# SW6124_A_A_C_MCU_LED.net
KiCad netlist of a schematic drawn in Altium Designer
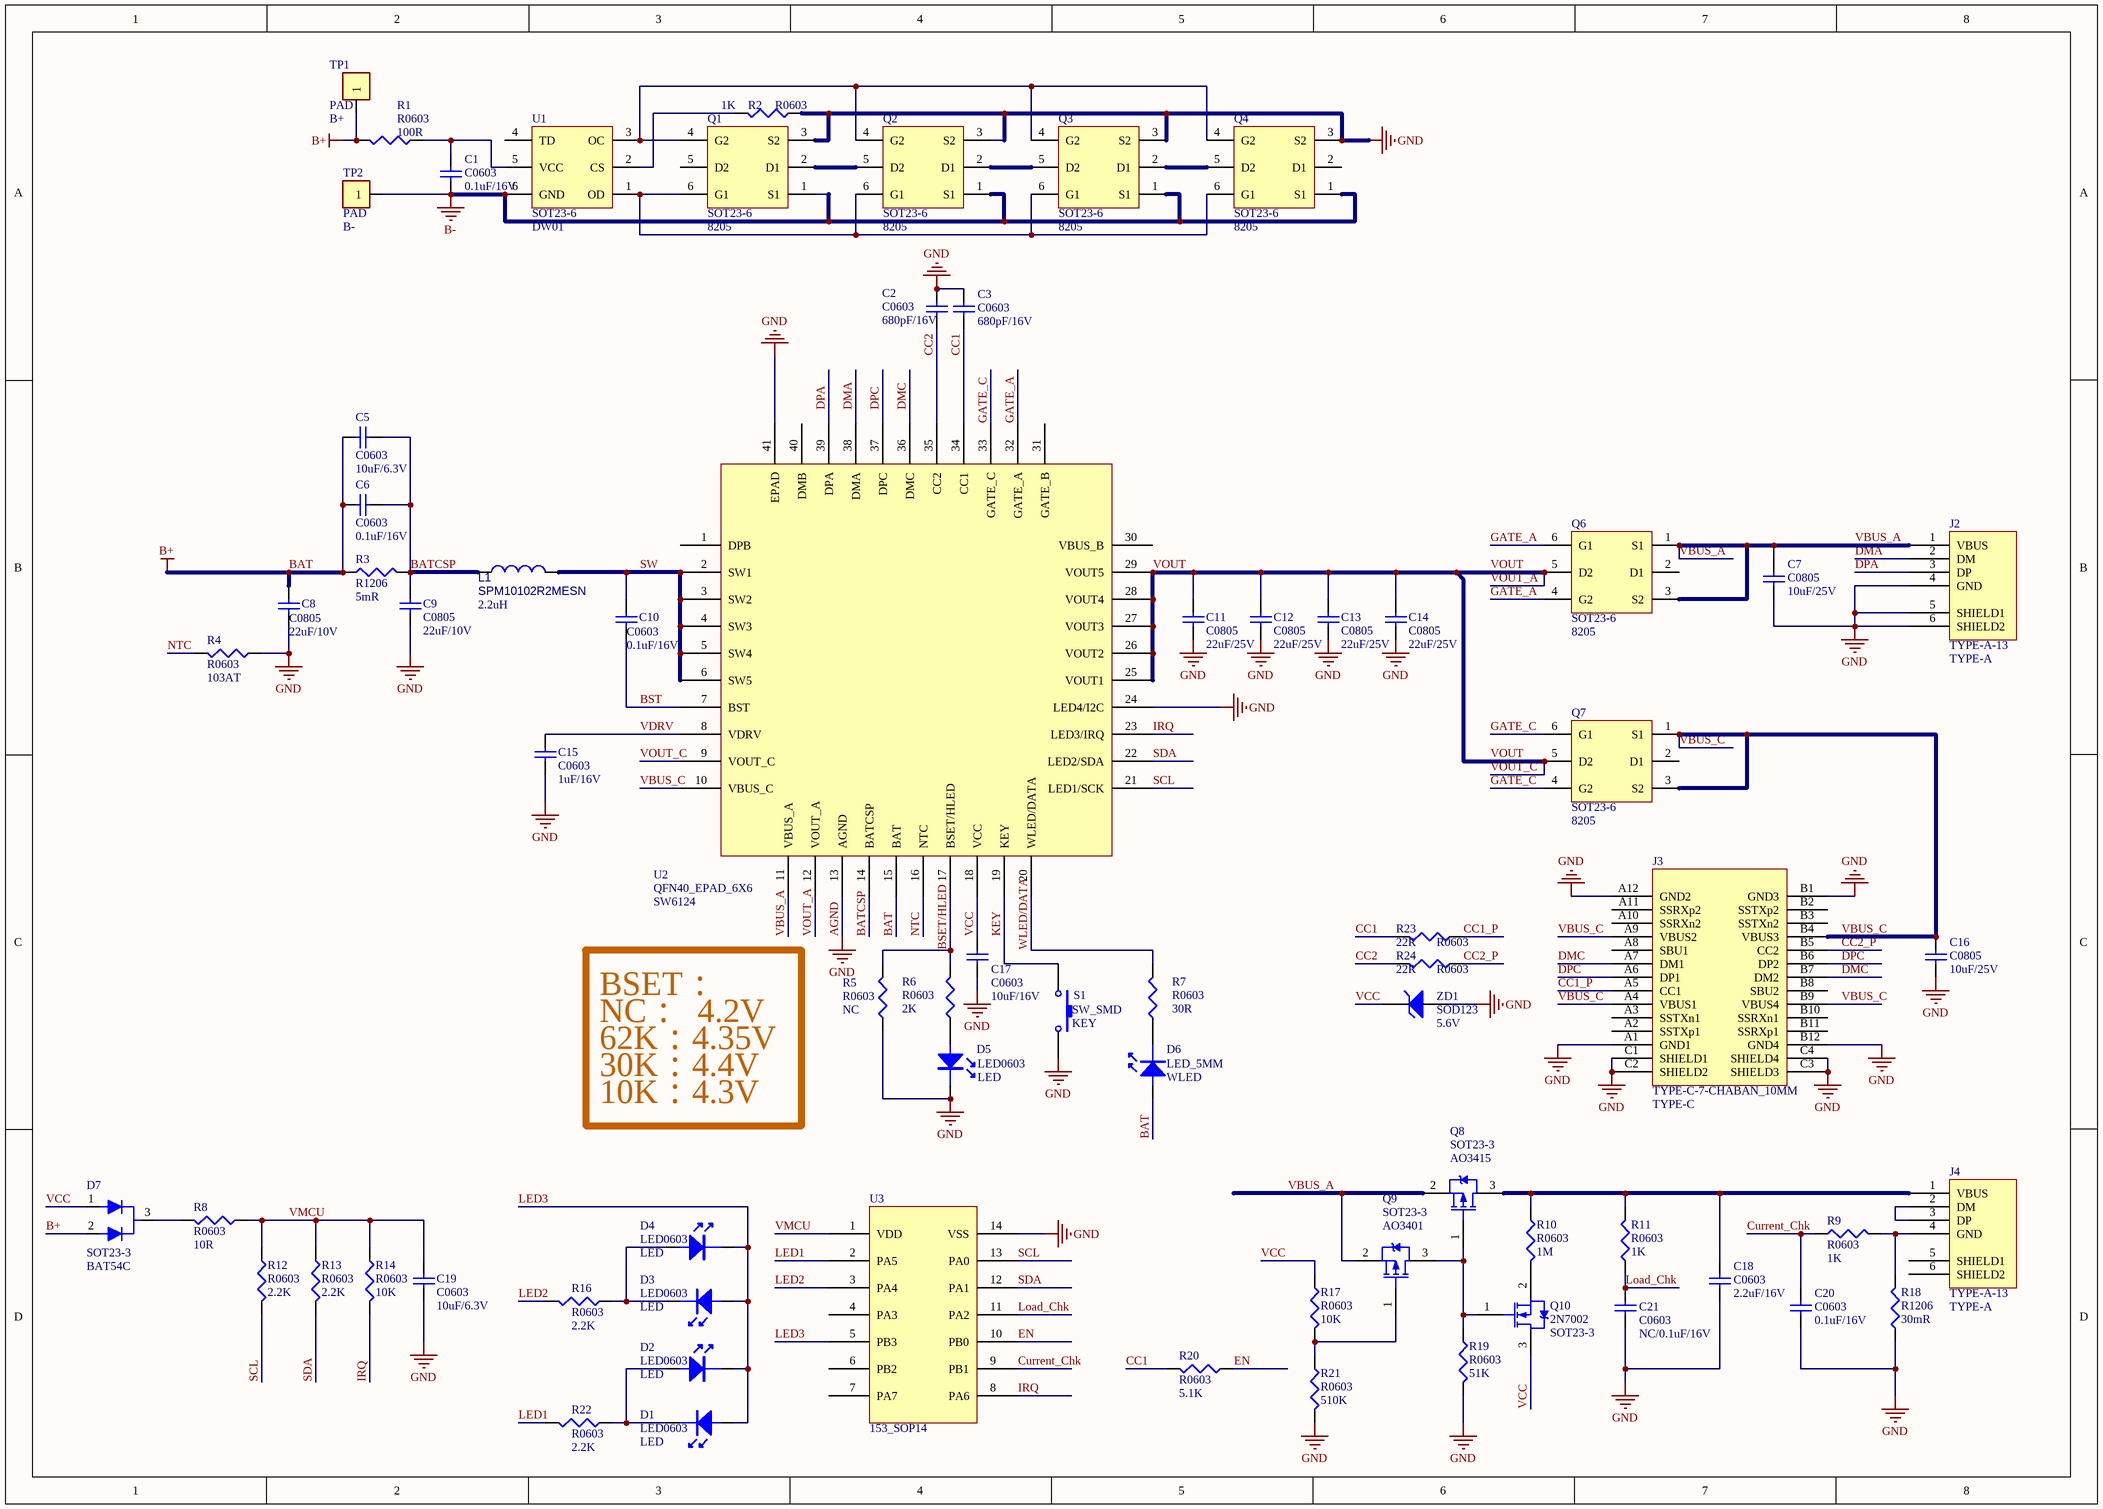
[diagram p0: SW6124+A+A+C+MCU+LED.SchDoc]

(export (version "E")
  (design (tool "Eeschema 10.0.6"))
  (components
    (comp (ref "C1")
      (value "C0603")
      (footprint "C0603")
      (description "Capacitor")
      (fields (field (name "ALTIUM_VALUE") "0.1uF/16V") (field (name "PUBLISHER") "Altium Limited"))
      (libsource (lib "*") (part "Cap"))
    )
    (comp (ref "C2")
      (value "C0603")
      (footprint "C0603")
      (description "Capacitor")
      (fields (field (name "ALTIUM_VALUE") "680pF/16V") (field (name "PUBLISHER") "Altium Limited"))
      (libsource (lib "*") (part "CAP0603"))
    )
    (comp (ref "C3")
      (value "C0603")
      (footprint "C0603")
      (description "Capacitor")
      (fields (field (name "ALTIUM_VALUE") "680pF/16V") (field (name "PUBLISHER") "Altium Limited"))
      (libsource (lib "*") (part "CAP0603"))
    )
    (comp (ref "C5")
      (value "C0603")
      (footprint "C0603")
      (description "Capacitor")
      (fields (field (name "ALTIUM_VALUE") "10uF/6.3V") (field (name "PUBLISHER") "Altium Limited"))
      (libsource (lib "*") (part "CAP0603"))
    )
    (comp (ref "C6")
      (value "C0603")
      (footprint "C0603")
      (description "Capacitor")
      (fields (field (name "ALTIUM_VALUE") "0.1uF/16V") (field (name "PUBLISHER") "Altium Limited"))
      (libsource (lib "*") (part "CAP0603"))
    )
    (comp (ref "C7")
      (value "C0805")
      (footprint "C0805")
      (description "Capacitor")
      (fields (field (name "ALTIUM_VALUE") "10uF/25V") (field (name "PUBLISHER") "Altium Limited"))
      (libsource (lib "*") (part "CAP0603"))
    )
    (comp (ref "C8")
      (value "C0805")
      (footprint "C0805")
      (description "Capacitor")
      (fields (field (name "ALTIUM_VALUE") "22uF/10V") (field (name "PUBLISHER") "Altium Limited"))
      (libsource (lib "*") (part "CAP0805"))
    )
    (comp (ref "C9")
      (value "C0805")
      (footprint "C0805")
      (description "Capacitor")
      (fields (field (name "ALTIUM_VALUE") "22uF/10V") (field (name "PUBLISHER") "Altium Limited"))
      (libsource (lib "*") (part "CAP0805"))
    )
    (comp (ref "C10")
      (value "C0603")
      (footprint "C0603")
      (description "Capacitor")
      (fields (field (name "ALTIUM_VALUE") "0.1uF/16V") (field (name "PUBLISHER") "Altium Limited"))
      (libsource (lib "*") (part "CAP0603"))
    )
    (comp (ref "C11")
      (value "C0805")
      (footprint "C0805")
      (description "Capacitor")
      (fields (field (name "ALTIUM_VALUE") "22uF/25V") (field (name "PUBLISHER") "Altium Limited"))
      (libsource (lib "*") (part "CAP0805"))
    )
    (comp (ref "C12")
      (value "C0805")
      (footprint "C0805")
      (description "Capacitor")
      (fields (field (name "ALTIUM_VALUE") "22uF/25V") (field (name "PUBLISHER") "Altium Limited"))
      (libsource (lib "*") (part "CAP0805"))
    )
    (comp (ref "C13")
      (value "C0805")
      (footprint "C0805")
      (description "Capacitor")
      (fields (field (name "ALTIUM_VALUE") "22uF/25V") (field (name "PUBLISHER") "Altium Limited"))
      (libsource (lib "*") (part "CAP0805"))
    )
    (comp (ref "C14")
      (value "C0805")
      (footprint "C0805")
      (description "Capacitor")
      (fields (field (name "ALTIUM_VALUE") "22uF/25V") (field (name "PUBLISHER") "Altium Limited"))
      (libsource (lib "*") (part "CAP0805"))
    )
    (comp (ref "C15")
      (value "C0603")
      (footprint "C0603")
      (description "Capacitor")
      (fields (field (name "ALTIUM_VALUE") "1uF/16V") (field (name "PUBLISHER") "Altium Limited"))
      (libsource (lib "*") (part "CAP0603"))
    )
    (comp (ref "C16")
      (value "C0805")
      (footprint "C0805")
      (description "Capacitor")
      (fields (field (name "ALTIUM_VALUE") "10uF/25V") (field (name "PUBLISHER") "Altium Limited"))
      (libsource (lib "*") (part "CAP0603"))
    )
    (comp (ref "C17")
      (value "C0603")
      (footprint "C0603")
      (description "Capacitor")
      (fields (field (name "ALTIUM_VALUE") "10uF/16V") (field (name "PUBLISHER") "Altium Limited"))
      (libsource (lib "*") (part "CAP0603"))
    )
    (comp (ref "C18")
      (value "C0603")
      (footprint "C0603")
      (description "Capacitor")
      (fields (field (name "ALTIUM_VALUE") "2.2uF/16V") (field (name "PUBLISHER") "Altium Limited"))
      (libsource (lib "*") (part "CAP0603"))
    )
    (comp (ref "C19")
      (value "C0603")
      (footprint "C0603")
      (description "Capacitor")
      (fields (field (name "ALTIUM_VALUE") "10uF/6.3V") (field (name "PUBLISHER") "Altium Limited"))
      (libsource (lib "*") (part "CAP0603"))
    )
    (comp (ref "C20")
      (value "C0603")
      (footprint "C0603")
      (description "Capacitor")
      (fields (field (name "ALTIUM_VALUE") "0.1uF/16V") (field (name "PUBLISHER") "Altium Limited"))
      (libsource (lib "*") (part "CAP0603"))
    )
    (comp (ref "C21")
      (value "C0603")
      (footprint "C0603")
      (description "Capacitor")
      (fields (field (name "ALTIUM_VALUE") "NC/0.1uF/16V") (field (name "PUBLISHER") "Altium Limited"))
      (libsource (lib "*") (part "CAP0603"))
    )
    (comp (ref "D1") (value "LED") (footprint "LED0603") (libsource (lib "*") (part "LED")))
    (comp (ref "D2") (value "LED") (footprint "LED0603") (libsource (lib "*") (part "LED")))
    (comp (ref "D3") (value "LED") (footprint "LED0603") (libsource (lib "*") (part "LED")))
    (comp (ref "D4") (value "LED") (footprint "LED0603") (libsource (lib "*") (part "LED")))
    (comp (ref "D5") (value "LED") (footprint "LED0603") (libsource (lib "*") (part "LED")))
    (comp (ref "D6")
      (value "WLED")
      (footprint "LED_5MM")
      (fields (field (name "FOOTPRINF") "LED_5MM") (field (name "Comment") "LED_5MM"))
      (libsource (lib "*") (part "LED"))
    )
    (comp (ref "D7") (value "BAT54C") (footprint "SOT23-3") (libsource (lib "Schlib1-2012") (part "D3")))
    (comp (ref "J2")
      (value "TYPE-A")
      (footprint "TYPE-A-13")
      (fields (field (name "FOOTPRINF") "TYPE-A-13") (field (name "Comment") "TYPE-A-1"))
      (libsource (lib "*") (part "TYPE-A-1"))
    )
    (comp (ref "J3")
      (value "TYPE-C")
      (footprint "TYPE-C-7-CHABAN_10MM")
      (libsource (lib "*") (part "TYPE-C"))
    )
    (comp (ref "J4")
      (value "TYPE-A")
      (footprint "PIE10-USB")
      (fields (field (name "FOOTPRINF") "TYPE-A-13") (field (name "Comment") "TYPE-A-1"))
      (libsource (lib "*") (part "TYPE-A-1"))
    )
    (comp (ref "L1")
      (value "SPM10102R2MESN")
      (footprint "INDUCTOR_SPM1010")
      (fields (field (name "ALTIUM_VALUE") "2.2uH"))
      (libsource (lib "*") (part "INDUCTOR"))
    )
    (comp (ref "Q1")
      (value "8205")
      (footprint "SOT23-6")
      (fields (field (name "FOOTPRINF") "SOT23-6"))
      (libsource (lib "") (part "8205B_1"))
    )
    (comp (ref "Q2")
      (value "8205")
      (footprint "SOT23-6")
      (fields (field (name "FOOTPRINF") "SOT23-6"))
      (libsource (lib "") (part "8205B_1"))
    )
    (comp (ref "Q3")
      (value "8205")
      (footprint "SOT23-6")
      (fields (field (name "FOOTPRINF") "SOT23-6"))
      (libsource (lib "") (part "8205B_1"))
    )
    (comp (ref "Q4")
      (value "8205")
      (footprint "SOT23-6")
      (fields (field (name "FOOTPRINF") "SOT23-6"))
      (libsource (lib "") (part "8205B_1"))
    )
    (comp (ref "Q6")
      (value "8205")
      (footprint "SOT23-6")
      (fields (field (name "FOOTPRINF") "SOT23-6"))
      (libsource (lib "*") (part "8205B"))
    )
    (comp (ref "Q7")
      (value "8205")
      (footprint "SOT23-6")
      (fields (field (name "FOOTPRINF") "SOT23-6"))
      (libsource (lib "*") (part "8205B"))
    )
    (comp (ref "Q8")
      (value "AO3415")
      (footprint "SOT23-3")
      (description "P-Channel Power MOSFET")
      (fields (field (name "Comment") "PMOS-2") (field (name "PUBLISHER") "Altium Limited"))
      (libsource (lib "Miscellaneous Devices") (part "PMOS-2"))
    )
    (comp (ref "Q9")
      (value "AO3401")
      (footprint "SOT23-3")
      (description "P-Channel Power MOSFET")
      (fields (field (name "Comment") "PMOS-2") (field (name "PUBLISHER") "Altium Limited"))
      (libsource (lib "Miscellaneous Devices") (part "PMOS-2"))
    )
    (comp (ref "Q10")
      (value "2N7002")
      (footprint "SOT23-3")
      (description "N-Channel Power MOSFET")
      (fields (field (name "Comment") "NMOS-2") (field (name "PUBLISHER") "Altium Limited"))
      (libsource (lib "Miscellaneous Devices") (part "NMOS-2"))
    )
    (comp (ref "R1")
      (value "R0603")
      (footprint "R0603")
      (description "Resistor")
      (fields (field (name "ALTIUM_VALUE") "100R") (field (name "PUBLISHER") "Altium Limited"))
      (libsource (lib "*") (part "Res3"))
    )
    (comp (ref "R2")
      (value "R0603")
      (footprint "R0603")
      (description "Resistor")
      (fields (field (name "ALTIUM_VALUE") "1K") (field (name "PUBLISHER") "Altium Limited"))
      (libsource (lib "*") (part "Res3"))
    )
    (comp (ref "R3")
      (value "R1206")
      (footprint "R1206")
      (description "Resistor")
      (fields (field (name "ALTIUM_VALUE") "5mR") (field (name "PUBLISHER") "Altium Limited"))
      (libsource (lib "*") (part "RES"))
    )
    (comp (ref "R4")
      (value "R0603")
      (footprint "R0603")
      (description "Resistor")
      (fields (field (name "ALTIUM_VALUE") "103AT") (field (name "PUBLISHER") "Altium Limited"))
      (libsource (lib "*") (part "RES"))
    )
    (comp (ref "R5")
      (value "R0603")
      (footprint "R0603")
      (description "Resistor")
      (fields (field (name "ALTIUM_VALUE") "NC") (field (name "PUBLISHER") "Altium Limited"))
      (libsource (lib "*") (part "RES"))
    )
    (comp (ref "R6")
      (value "R0603")
      (footprint "R0603")
      (description "Resistor")
      (fields (field (name "ALTIUM_VALUE") "2K") (field (name "PUBLISHER") "Altium Limited"))
      (libsource (lib "*") (part "RES"))
    )
    (comp (ref "R7")
      (value "R0603")
      (footprint "R0603")
      (description "Resistor")
      (fields (field (name "ALTIUM_VALUE") "30R") (field (name "PUBLISHER") "Altium Limited"))
      (libsource (lib "*") (part "RES"))
    )
    (comp (ref "R8")
      (value "R0603")
      (footprint "R0603")
      (description "Resistor")
      (fields (field (name "ALTIUM_VALUE") "10R") (field (name "PUBLISHER") "Altium Limited"))
      (libsource (lib "*") (part "RES"))
    )
    (comp (ref "R9")
      (value "R0603")
      (footprint "R0603")
      (description "Resistor")
      (fields (field (name "ALTIUM_VALUE") "1K") (field (name "PUBLISHER") "Altium Limited"))
      (libsource (lib "*") (part "RES"))
    )
    (comp (ref "R10")
      (value "R0603")
      (footprint "R0603")
      (description "Resistor")
      (fields (field (name "ALTIUM_VALUE") "1M") (field (name "PUBLISHER") "Altium Limited"))
      (libsource (lib "*") (part "RES"))
    )
    (comp (ref "R11")
      (value "R0603")
      (footprint "R0603")
      (description "Resistor")
      (fields (field (name "ALTIUM_VALUE") "1K") (field (name "PUBLISHER") "Altium Limited"))
      (libsource (lib "*") (part "RES"))
    )
    (comp (ref "R12")
      (value "R0603")
      (footprint "R0603")
      (description "Resistor")
      (fields (field (name "ALTIUM_VALUE") "2.2K") (field (name "PUBLISHER") "Altium Limited"))
      (libsource (lib "*") (part "RES"))
    )
    (comp (ref "R13")
      (value "R0603")
      (footprint "R0603")
      (description "Resistor")
      (fields (field (name "ALTIUM_VALUE") "2.2K") (field (name "PUBLISHER") "Altium Limited"))
      (libsource (lib "*") (part "RES"))
    )
    (comp (ref "R14")
      (value "R0603")
      (footprint "R0603")
      (description "Resistor")
      (fields (field (name "ALTIUM_VALUE") "10K") (field (name "PUBLISHER") "Altium Limited"))
      (libsource (lib "*") (part "RES"))
    )
    (comp (ref "R16")
      (value "R0603")
      (footprint "R0603")
      (description "Resistor")
      (fields (field (name "ALTIUM_VALUE") "2.2K") (field (name "PUBLISHER") "Altium Limited"))
      (libsource (lib "*") (part "RES"))
    )
    (comp (ref "R17")
      (value "R0603")
      (footprint "R0603")
      (description "Resistor")
      (fields (field (name "ALTIUM_VALUE") "10K") (field (name "PUBLISHER") "Altium Limited"))
      (libsource (lib "*") (part "RES"))
    )
    (comp (ref "R18")
      (value "R1206")
      (footprint "C-1206A")
      (description "Resistor")
      (fields (field (name "ALTIUM_VALUE") "30mR") (field (name "PUBLISHER") "Altium Limited"))
      (libsource (lib "*") (part "RES"))
    )
    (comp (ref "R19")
      (value "R0603")
      (footprint "R0603")
      (description "Resistor")
      (fields (field (name "ALTIUM_VALUE") "51K") (field (name "PUBLISHER") "Altium Limited"))
      (libsource (lib "*") (part "RES"))
    )
    (comp (ref "R20")
      (value "R0603")
      (footprint "R0603")
      (description "Resistor")
      (fields (field (name "ALTIUM_VALUE") "5.1K") (field (name "PUBLISHER") "Altium Limited"))
      (libsource (lib "*") (part "RES"))
    )
    (comp (ref "R21")
      (value "R0603")
      (footprint "R0603")
      (description "Resistor")
      (fields (field (name "ALTIUM_VALUE") "510K") (field (name "PUBLISHER") "Altium Limited"))
      (libsource (lib "*") (part "RES"))
    )
    (comp (ref "R22")
      (value "R0603")
      (footprint "R0603")
      (description "Resistor")
      (fields (field (name "ALTIUM_VALUE") "2.2K") (field (name "PUBLISHER") "Altium Limited"))
      (libsource (lib "*") (part "RES"))
    )
    (comp (ref "R23")
      (value "R0603")
      (footprint "R0603")
      (description "Resistor")
      (fields (field (name "ALTIUM_VALUE") "22R") (field (name "PUBLISHER") "Altium Limited"))
      (libsource (lib "*") (part "RES"))
    )
    (comp (ref "R24")
      (value "R0603")
      (footprint "R0603")
      (description "Resistor")
      (fields (field (name "ALTIUM_VALUE") "22R") (field (name "PUBLISHER") "Altium Limited"))
      (libsource (lib "*") (part "RES"))
    )
    (comp (ref "S1")
      (value "KEY")
      (footprint "SW_SMD")
      (fields (field (name "FOOTPRINF") "SW_SMD"))
      (libsource (lib "*") (part "SW K"))
    )
    (comp (ref "TP1") (value "B+") (footprint "PAD") (libsource (lib "") (part "Test Point_1")))
    (comp (ref "TP2") (value "B-") (footprint "PAD") (libsource (lib "*") (part "Test Point")))
    (comp (ref "U1")
      (value "DW01")
      (footprint "SOT23-6")
      (fields (field (name "FOOTPRINF") "SOT23-6"))
      (libsource (lib "*") (part "DW01"))
    )
    (comp (ref "U2")
      (value "SW6124")
      (footprint "QFN40_EPAD_6X6")
      (libsource (lib "TEST") (part "SW6106_AFC"))
    )
    (comp (ref "U3") (value "153_SOP14") (libsource (lib "TEST") (part "153_SOP14")))
    (comp (ref "ZD1")
      (value "SOD123")
      (footprint "SOD-123")
      (description "Zener Diode")
      (fields (field (name "ALTIUM_UNNAMED_1") "5.6V"))
      (libsource (lib "Miscellaneous Devices") (part "D Zener"))
    )
  )
  (nets
    (net (code "1") (name "/BATCSP") (class "Default")
      (node (ref "C5") (pin "2") (pinfunction "2_2") (pintype "passive"))
      (node (ref "C6") (pin "2") (pinfunction "2_2") (pintype "passive"))
      (node (ref "C9") (pin "2") (pinfunction "2_2") (pintype "passive"))
      (node (ref "L1") (pin "1") (pinfunction "1_1") (pintype "passive"))
      (node (ref "R3") (pin "2") (pinfunction "2_2") (pintype "passive"))
      (node (ref "U2") (pin "14") (pinfunction "BATCSP_14") (pintype "passive"))
    )
    (net (code "2") (name "/BSET{slash}HLED") (class "Default")
      (node (ref "R5") (pin "2") (pinfunction "2_2") (pintype "passive"))
      (node (ref "R6") (pin "2") (pinfunction "2_2") (pintype "passive"))
      (node (ref "U2") (pin "17") (pinfunction "BSET/HLED_17") (pintype "passive"))
    )
    (net (code "3") (name "/BST") (class "Default")
      (node (ref "C10") (pin "1") (pinfunction "1_1") (pintype "passive"))
      (node (ref "U2") (pin "7") (pinfunction "BST_7") (pintype "passive"))
    )
    (net (code "4") (name "/CC1") (class "Default")
      (node (ref "C3") (pin "1") (pinfunction "1_1") (pintype "passive"))
      (node (ref "R20") (pin "2") (pinfunction "2_2") (pintype "passive"))
      (node (ref "R23") (pin "2") (pinfunction "2_2") (pintype "passive"))
      (node (ref "U2") (pin "34") (pinfunction "CC1_34") (pintype "passive"))
    )
    (net (code "5") (name "/CC1_P") (class "Default")
      (node (ref "J3") (pin "A5") (pinfunction "CC1_A5") (pintype "passive"))
      (node (ref "R23") (pin "1") (pinfunction "1_1") (pintype "passive"))
    )
    (net (code "6") (name "/CC2") (class "Default")
      (node (ref "C2") (pin "1") (pinfunction "1_1") (pintype "passive"))
      (node (ref "R24") (pin "2") (pinfunction "2_2") (pintype "passive"))
      (node (ref "U2") (pin "35") (pinfunction "CC2_35") (pintype "passive"))
    )
    (net (code "7") (name "/CC2_P") (class "Default")
      (node (ref "J3") (pin "B5") (pinfunction "CC2_B5") (pintype "passive"))
      (node (ref "R24") (pin "1") (pinfunction "1_1") (pintype "passive"))
    )
    (net (code "8") (name "/Current_Chk") (class "Default")
      (node (ref "C20") (pin "2") (pinfunction "2_2") (pintype "passive"))
      (node (ref "R9") (pin "1") (pinfunction "1_1") (pintype "passive"))
      (node (ref "U3") (pin "9") (pinfunction "PB1_9") (pintype "passive"))
    )
    (net (code "9") (name "/DMA") (class "Default")
      (node (ref "J2") (pin "2") (pinfunction "DM_2") (pintype "passive"))
      (node (ref "U2") (pin "38") (pinfunction "DMA_38") (pintype "passive"))
    )
    (net (code "10") (name "/DMC") (class "Default")
      (node (ref "J3") (pin "A7") (pinfunction "DM1_A7") (pintype "passive"))
      (node (ref "J3") (pin "B7") (pinfunction "DM2_B7") (pintype "passive"))
      (node (ref "U2") (pin "36") (pinfunction "DMC_36") (pintype "passive"))
    )
    (net (code "11") (name "/DPA") (class "Default")
      (node (ref "J2") (pin "3") (pinfunction "DP_3") (pintype "passive"))
      (node (ref "U2") (pin "39") (pinfunction "DPA_39") (pintype "passive"))
    )
    (net (code "12") (name "/DPC") (class "Default")
      (node (ref "J3") (pin "A6") (pinfunction "DP1_A6") (pintype "passive"))
      (node (ref "J3") (pin "B6") (pinfunction "DP2_B6") (pintype "passive"))
      (node (ref "U2") (pin "37") (pinfunction "DPC_37") (pintype "passive"))
    )
    (net (code "13") (name "/EN") (class "Default")
      (node (ref "R20") (pin "1") (pinfunction "1_1") (pintype "passive"))
      (node (ref "U3") (pin "10") (pinfunction "PB0_10") (pintype "passive"))
    )
    (net (code "14") (name "/GATE_A") (class "Default")
      (node (ref "Q6") (pin "4") (pinfunction "G2_4") (pintype "passive"))
      (node (ref "Q6") (pin "6") (pinfunction "G1_6") (pintype "passive"))
      (node (ref "U2") (pin "32") (pinfunction "GATE_A_32") (pintype "passive"))
    )
    (net (code "15") (name "/GATE_C") (class "Default")
      (node (ref "Q7") (pin "4") (pinfunction "G2_4") (pintype "passive"))
      (node (ref "Q7") (pin "6") (pinfunction "G1_6") (pintype "passive"))
      (node (ref "U2") (pin "33") (pinfunction "GATE_C_33") (pintype "passive"))
    )
    (net (code "16") (name "/IRQ") (class "Default")
      (node (ref "R14") (pin "2") (pinfunction "2_2") (pintype "passive"))
      (node (ref "U2") (pin "23") (pinfunction "LED3/IRQ_23") (pintype "passive"))
      (node (ref "U3") (pin "8") (pinfunction "PA6_8") (pintype "passive"))
    )
    (net (code "17") (name "/KEY") (class "Default")
      (node (ref "S1") (pin "1") (pinfunction "1_1") (pintype "passive"))
      (node (ref "U2") (pin "19") (pinfunction "KEY_19") (pintype "passive"))
    )
    (net (code "18") (name "/LED1") (class "Default")
      (node (ref "R22") (pin "2") (pinfunction "2_2") (pintype "passive"))
      (node (ref "U3") (pin "2") (pinfunction "PA5_2") (pintype "passive"))
    )
    (net (code "19") (name "/LED2") (class "Default")
      (node (ref "R16") (pin "2") (pinfunction "2_2") (pintype "passive"))
      (node (ref "U3") (pin "3") (pinfunction "PA4_3") (pintype "passive"))
    )
    (net (code "20") (name "/LED3") (class "Default")
      (node (ref "D1") (pin "1") (pinfunction "A_1") (pintype "passive"))
      (node (ref "D2") (pin "2") (pinfunction "K_2") (pintype "passive"))
      (node (ref "D3") (pin "1") (pinfunction "A_1") (pintype "passive"))
      (node (ref "D4") (pin "2") (pinfunction "K_2") (pintype "passive"))
      (node (ref "U3") (pin "5") (pinfunction "PB3_5") (pintype "passive"))
    )
    (net (code "21") (name "/Load_Chk") (class "Default")
      (node (ref "C21") (pin "2") (pinfunction "2_2") (pintype "passive"))
      (node (ref "R11") (pin "1") (pinfunction "1_1") (pintype "passive"))
      (node (ref "U3") (pin "11") (pinfunction "PA2_11") (pintype "passive"))
    )
    (net (code "22") (name "/NTC") (class "Default")
      (node (ref "R4") (pin "2") (pinfunction "2_2") (pintype "passive"))
      (node (ref "U2") (pin "16") (pinfunction "NTC_16") (pintype "passive"))
    )
    (net (code "23") (name "/SCL") (class "Default")
      (node (ref "R12") (pin "2") (pinfunction "2_2") (pintype "passive"))
      (node (ref "U2") (pin "21") (pinfunction "LED1/SCK_21") (pintype "passive"))
      (node (ref "U3") (pin "13") (pinfunction "PA0_13") (pintype "passive"))
    )
    (net (code "24") (name "/SDA") (class "Default")
      (node (ref "R13") (pin "2") (pinfunction "2_2") (pintype "passive"))
      (node (ref "U2") (pin "22") (pinfunction "LED2/SDA_22") (pintype "passive"))
      (node (ref "U3") (pin "12") (pinfunction "PA1_12") (pintype "passive"))
    )
    (net (code "25") (name "/SW") (class "Default")
      (node (ref "C10") (pin "2") (pinfunction "2_2") (pintype "passive"))
      (node (ref "L1") (pin "2") (pinfunction "2_2") (pintype "passive"))
      (node (ref "U2") (pin "2") (pinfunction "SW1_2") (pintype "passive"))
      (node (ref "U2") (pin "3") (pinfunction "SW2_3") (pintype "passive"))
      (node (ref "U2") (pin "4") (pinfunction "SW3_4") (pintype "passive"))
      (node (ref "U2") (pin "5") (pinfunction "SW4_5") (pintype "passive"))
      (node (ref "U2") (pin "6") (pinfunction "SW5_6") (pintype "passive"))
    )
    (net (code "26") (name "/VBUS_A") (class "Default")
      (node (ref "C7") (pin "2") (pinfunction "2_2") (pintype "passive"))
      (node (ref "J2") (pin "1") (pinfunction "VBUS_1") (pintype "passive"))
      (node (ref "Q6") (pin "1") (pinfunction "S1_1") (pintype "passive"))
      (node (ref "Q6") (pin "3") (pinfunction "S2_3") (pintype "passive"))
      (node (ref "Q8") (pin "2") (pinfunction "S_2") (pintype "passive"))
      (node (ref "Q9") (pin "2") (pinfunction "S_2") (pintype "passive"))
      (node (ref "U2") (pin "11") (pinfunction "VBUS_A_11") (pintype "passive"))
    )
    (net (code "27") (name "/VBUS_C") (class "Default")
      (node (ref "C16") (pin "2") (pinfunction "2_2") (pintype "passive"))
      (node (ref "J3") (pin "A4") (pinfunction "VBUS1_A4") (pintype "passive"))
      (node (ref "J3") (pin "A9") (pinfunction "VBUS2_A9") (pintype "passive"))
      (node (ref "J3") (pin "B4") (pinfunction "VBUS3_B4") (pintype "passive"))
      (node (ref "J3") (pin "B9") (pinfunction "VBUS4_B9") (pintype "passive"))
      (node (ref "Q7") (pin "1") (pinfunction "S1_1") (pintype "passive"))
      (node (ref "Q7") (pin "3") (pinfunction "S2_3") (pintype "passive"))
      (node (ref "U2") (pin "10") (pinfunction "VBUS_C_10") (pintype "passive"))
    )
    (net (code "28") (name "/VCC") (class "Default")
      (node (ref "C17") (pin "2") (pinfunction "2_2") (pintype "passive"))
      (node (ref "D7") (pin "1") (pintype "passive"))
      (node (ref "Q10") (pin "3") (pinfunction "D_3") (pintype "passive"))
      (node (ref "R17") (pin "1") (pinfunction "1_1") (pintype "passive"))
      (node (ref "U2") (pin "18") (pinfunction "VCC_18") (pintype "passive"))
      (node (ref "ZD1") (pin "2") (pinfunction "K_2") (pintype "passive"))
    )
    (net (code "29") (name "/VDRV") (class "Default")
      (node (ref "C15") (pin "2") (pinfunction "2_2") (pintype "passive"))
      (node (ref "U2") (pin "8") (pinfunction "VDRV_8") (pintype "passive"))
    )
    (net (code "30") (name "/VMCU") (class "Default")
      (node (ref "C19") (pin "1") (pinfunction "1_1") (pintype "passive"))
      (node (ref "R12") (pin "1") (pinfunction "1_1") (pintype "passive"))
      (node (ref "R13") (pin "1") (pinfunction "1_1") (pintype "passive"))
      (node (ref "R14") (pin "1") (pinfunction "1_1") (pintype "passive"))
      (node (ref "R8") (pin "1") (pinfunction "1_1") (pintype "passive"))
      (node (ref "U3") (pin "1") (pinfunction "VDD_1") (pintype "passive"))
    )
    (net (code "31") (name "/VOUT") (class "Default")
      (node (ref "C11") (pin "2") (pinfunction "2_2") (pintype "passive"))
      (node (ref "C12") (pin "2") (pinfunction "2_2") (pintype "passive"))
      (node (ref "C13") (pin "2") (pinfunction "2_2") (pintype "passive"))
      (node (ref "C14") (pin "2") (pinfunction "2_2") (pintype "passive"))
      (node (ref "Q6") (pin "5") (pinfunction "D2_5") (pintype "passive"))
      (node (ref "Q7") (pin "5") (pinfunction "D2_5") (pintype "passive"))
      (node (ref "U2") (pin "12") (pinfunction "VOUT_A_12") (pintype "passive"))
      (node (ref "U2") (pin "25") (pinfunction "VOUT1_25") (pintype "passive"))
      (node (ref "U2") (pin "26") (pinfunction "VOUT2_26") (pintype "passive"))
      (node (ref "U2") (pin "27") (pinfunction "VOUT3_27") (pintype "passive"))
      (node (ref "U2") (pin "28") (pinfunction "VOUT4_28") (pintype "passive"))
      (node (ref "U2") (pin "29") (pinfunction "VOUT5_29") (pintype "passive"))
      (node (ref "U2") (pin "9") (pinfunction "VOUT_C_9") (pintype "passive"))
    )
    (net (code "32") (name "/WLED{slash}DATA") (class "Default")
      (node (ref "R7") (pin "2") (pinfunction "2_2") (pintype "passive"))
      (node (ref "U2") (pin "20") (pinfunction "WLED/DATA_20") (pintype "passive"))
    )
    (net (code "33") (name "B+") (class "Default")
      (node (ref "C5") (pin "1") (pinfunction "1_1") (pintype "passive"))
      (node (ref "C6") (pin "1") (pinfunction "1_1") (pintype "passive"))
      (node (ref "C8") (pin "2") (pinfunction "2_2") (pintype "passive"))
      (node (ref "D6") (pin "1") (pinfunction "A_1") (pintype "passive"))
      (node (ref "D7") (pin "2") (pintype "passive"))
      (node (ref "R1") (pin "2") (pinfunction "2_2") (pintype "passive"))
      (node (ref "R3") (pin "1") (pinfunction "1_1") (pintype "passive"))
      (node (ref "TP1") (pin "1") (pinfunction "1_1") (pintype "passive"))
      (node (ref "U2") (pin "15") (pinfunction "BAT_15") (pintype "passive"))
    )
    (net (code "34") (name "B-") (class "Default")
      (node (ref "C1") (pin "1") (pinfunction "1_1") (pintype "passive"))
      (node (ref "Q1") (pin "1") (pinfunction "S1_1") (pintype "passive"))
      (node (ref "Q2") (pin "1") (pinfunction "S1_1") (pintype "passive"))
      (node (ref "Q3") (pin "1") (pinfunction "S1_1") (pintype "passive"))
      (node (ref "Q4") (pin "1") (pinfunction "S1_1") (pintype "passive"))
      (node (ref "TP2") (pin "1") (pinfunction "1_1") (pintype "passive"))
      (node (ref "U1") (pin "6") (pinfunction "GND_6") (pintype "passive"))
    )
    (net (code "35") (name "GND") (class "Default")
      (node (ref "C11") (pin "1") (pinfunction "1_1") (pintype "passive"))
      (node (ref "C12") (pin "1") (pinfunction "1_1") (pintype "passive"))
      (node (ref "C13") (pin "1") (pinfunction "1_1") (pintype "passive"))
      (node (ref "C14") (pin "1") (pinfunction "1_1") (pintype "passive"))
      (node (ref "C15") (pin "1") (pinfunction "1_1") (pintype "passive"))
      (node (ref "C16") (pin "1") (pinfunction "1_1") (pintype "passive"))
      (node (ref "C17") (pin "1") (pinfunction "1_1") (pintype "passive"))
      (node (ref "C18") (pin "1") (pinfunction "1_1") (pintype "passive"))
      (node (ref "C19") (pin "2") (pinfunction "2_2") (pintype "passive"))
      (node (ref "C2") (pin "2") (pinfunction "2_2") (pintype "passive"))
      (node (ref "C20") (pin "1") (pinfunction "1_1") (pintype "passive"))
      (node (ref "C21") (pin "1") (pinfunction "1_1") (pintype "passive"))
      (node (ref "C3") (pin "2") (pinfunction "2_2") (pintype "passive"))
      (node (ref "C7") (pin "1") (pinfunction "1_1") (pintype "passive"))
      (node (ref "C8") (pin "1") (pinfunction "1_1") (pintype "passive"))
      (node (ref "C9") (pin "1") (pinfunction "1_1") (pintype "passive"))
      (node (ref "D5") (pin "2") (pinfunction "K_2") (pintype "passive"))
      (node (ref "J2") (pin "4") (pinfunction "GND_4") (pintype "passive"))
      (node (ref "J2") (pin "5") (pinfunction "SHIELD1_5") (pintype "passive"))
      (node (ref "J2") (pin "6") (pinfunction "SHIELD2_6") (pintype "passive"))
      (node (ref "J3") (pin "A1") (pinfunction "GND1_A1") (pintype "passive"))
      (node (ref "J3") (pin "A12") (pinfunction "GND2_A12") (pintype "passive"))
      (node (ref "J3") (pin "B1") (pinfunction "GND3_B1") (pintype "passive"))
      (node (ref "J3") (pin "B12") (pinfunction "GND4_B12") (pintype "passive"))
      (node (ref "J3") (pin "C1") (pinfunction "SHIELD1_C1") (pintype "passive"))
      (node (ref "J3") (pin "C2") (pinfunction "SHIELD2_C2") (pintype "passive"))
      (node (ref "J3") (pin "C3") (pinfunction "SHIELD3_C3") (pintype "passive"))
      (node (ref "J3") (pin "C4") (pinfunction "SHIELD4_C4") (pintype "passive"))
      (node (ref "Q1") (pin "3") (pinfunction "S2_3") (pintype "passive"))
      (node (ref "Q2") (pin "3") (pinfunction "S2_3") (pintype "passive"))
      (node (ref "Q3") (pin "3") (pinfunction "S2_3") (pintype "passive"))
      (node (ref "Q4") (pin "3") (pinfunction "S2_3") (pintype "passive"))
      (node (ref "R18") (pin "1") (pinfunction "1_1") (pintype "passive"))
      (node (ref "R19") (pin "2") (pinfunction "2_2") (pintype "passive"))
      (node (ref "R2") (pin "1") (pinfunction "1_1") (pintype "passive"))
      (node (ref "R21") (pin "2") (pinfunction "2_2") (pintype "passive"))
      (node (ref "R4") (pin "1") (pinfunction "1_1") (pintype "passive"))
      (node (ref "R5") (pin "1") (pinfunction "1_1") (pintype "passive"))
      (node (ref "S1") (pin "2") (pinfunction "2_2") (pintype "passive"))
      (node (ref "U2") (pin "13") (pinfunction "AGND_13") (pintype "passive"))
      (node (ref "U2") (pin "24") (pinfunction "LED4/I2C_24") (pintype "passive"))
      (node (ref "U2") (pin "41") (pinfunction "EPAD_41") (pintype "passive"))
      (node (ref "U3") (pin "14") (pinfunction "VSS_14") (pintype "passive"))
      (node (ref "ZD1") (pin "1") (pinfunction "A_1") (pintype "passive"))
    )
    (net (code "36") (name "Net-(D1-K)") (class "Default")
      (node (ref "D1") (pin "2") (pinfunction "K_2") (pintype "passive"))
      (node (ref "D2") (pin "1") (pinfunction "A_1") (pintype "passive"))
      (node (ref "R22") (pin "1") (pinfunction "1_1") (pintype "passive"))
    )
    (net (code "37") (name "Net-(D3-K)") (class "Default")
      (node (ref "D3") (pin "2") (pinfunction "K_2") (pintype "passive"))
      (node (ref "D4") (pin "1") (pinfunction "A_1") (pintype "passive"))
      (node (ref "R16") (pin "1") (pinfunction "1_1") (pintype "passive"))
    )
    (net (code "38") (name "Net-(D5-A)") (class "Default")
      (node (ref "D5") (pin "1") (pinfunction "A_1") (pintype "passive"))
      (node (ref "R6") (pin "1") (pinfunction "1_1") (pintype "passive"))
    )
    (net (code "39") (name "Net-(D6-K)") (class "Default")
      (node (ref "D6") (pin "2") (pinfunction "K_2") (pintype "passive"))
      (node (ref "R7") (pin "1") (pinfunction "1_1") (pintype "passive"))
    )
    (net (code "40") (name "Net-(D7-Pad3)") (class "Default")
      (node (ref "D7") (pin "3") (pintype "passive"))
      (node (ref "R8") (pin "2") (pinfunction "2_2") (pintype "passive"))
    )
    (net (code "41") (name "Net-(J4-DM)") (class "Default")
      (node (ref "J4") (pin "2") (pinfunction "DM_2") (pintype "passive"))
      (node (ref "J4") (pin "3") (pinfunction "DP_3") (pintype "passive"))
    )
    (net (code "42") (name "Net-(J4-GND)") (class "Default")
      (node (ref "J4") (pin "4") (pinfunction "GND_4") (pintype "passive"))
      (node (ref "R18") (pin "2") (pinfunction "2_2") (pintype "passive"))
      (node (ref "R9") (pin "2") (pinfunction "2_2") (pintype "passive"))
    )
    (net (code "43") (name "Net-(J4-VBUS)") (class "Default")
      (node (ref "C18") (pin "2") (pinfunction "2_2") (pintype "passive"))
      (node (ref "J4") (pin "1") (pinfunction "VBUS_1") (pintype "passive"))
      (node (ref "Q8") (pin "3") (pinfunction "D_3") (pintype "passive"))
      (node (ref "R10") (pin "1") (pinfunction "1_1") (pintype "passive"))
      (node (ref "R11") (pin "2") (pinfunction "2_2") (pintype "passive"))
    )
    (net (code "44") (name "Net-(Q1-D1)") (class "Default")
      (node (ref "Q1") (pin "2") (pinfunction "D1_2") (pintype "passive"))
      (node (ref "Q2") (pin "5") (pinfunction "D2_5") (pintype "passive"))
    )
    (net (code "45") (name "Net-(Q1-G1)") (class "Default")
      (node (ref "Q1") (pin "6") (pinfunction "G1_6") (pintype "passive"))
      (node (ref "Q2") (pin "6") (pinfunction "G1_6") (pintype "passive"))
      (node (ref "Q3") (pin "6") (pinfunction "G1_6") (pintype "passive"))
      (node (ref "Q4") (pin "6") (pinfunction "G1_6") (pintype "passive"))
      (node (ref "U1") (pin "1") (pinfunction "OD_1") (pintype "passive"))
    )
    (net (code "46") (name "Net-(Q1-G2)") (class "Default")
      (node (ref "Q1") (pin "4") (pinfunction "G2_4") (pintype "passive"))
      (node (ref "Q2") (pin "4") (pinfunction "G2_4") (pintype "passive"))
      (node (ref "Q3") (pin "4") (pinfunction "G2_4") (pintype "passive"))
      (node (ref "Q4") (pin "4") (pinfunction "G2_4") (pintype "passive"))
      (node (ref "U1") (pin "3") (pinfunction "OC_3") (pintype "passive"))
    )
    (net (code "47") (name "Net-(Q2-D1)") (class "Default")
      (node (ref "Q2") (pin "2") (pinfunction "D1_2") (pintype "passive"))
      (node (ref "Q3") (pin "5") (pinfunction "D2_5") (pintype "passive"))
    )
    (net (code "48") (name "Net-(Q3-D1)") (class "Default")
      (node (ref "Q3") (pin "2") (pinfunction "D1_2") (pintype "passive"))
      (node (ref "Q4") (pin "5") (pinfunction "D2_5") (pintype "passive"))
    )
    (net (code "49") (name "Net-(Q9-G)") (class "Default")
      (node (ref "Q9") (pin "1") (pinfunction "G_1") (pintype "passive"))
      (node (ref "R17") (pin "2") (pinfunction "2_2") (pintype "passive"))
      (node (ref "R21") (pin "1") (pinfunction "1_1") (pintype "passive"))
    )
    (net (code "50") (name "Net-(Q10-G)") (class "Default")
      (node (ref "Q10") (pin "1") (pinfunction "G_1") (pintype "passive"))
      (node (ref "Q8") (pin "1") (pinfunction "G_1") (pintype "passive"))
      (node (ref "Q9") (pin "3") (pinfunction "D_3") (pintype "passive"))
      (node (ref "R19") (pin "1") (pinfunction "1_1") (pintype "passive"))
    )
    (net (code "51") (name "Net-(Q10-S)") (class "Default")
      (node (ref "Q10") (pin "2") (pinfunction "S_2") (pintype "passive"))
      (node (ref "R10") (pin "2") (pinfunction "2_2") (pintype "passive"))
    )
    (net (code "52") (name "Net-(U1-CS)") (class "Default")
      (node (ref "R2") (pin "2") (pinfunction "2_2") (pintype "passive"))
      (node (ref "U1") (pin "2") (pinfunction "CS_2") (pintype "passive"))
    )
    (net (code "53") (name "Net-(U1-VCC)") (class "Default")
      (node (ref "C1") (pin "2") (pinfunction "2_2") (pintype "passive"))
      (node (ref "R1") (pin "1") (pinfunction "1_1") (pintype "passive"))
      (node (ref "U1") (pin "5") (pinfunction "VCC_5") (pintype "passive"))
    )
    (net (code "54") (name "unconnected-(J3-SBU1-PadA8)") (class "Default")
      (node (ref "J3") (pin "A8") (pinfunction "SBU1_A8") (pintype "passive"))
    )
    (net (code "55") (name "unconnected-(J3-SBU2-PadB8)") (class "Default")
      (node (ref "J3") (pin "B8") (pinfunction "SBU2_B8") (pintype "passive"))
    )
    (net (code "56") (name "unconnected-(J3-SSRXn1-PadB10)") (class "Default")
      (node (ref "J3") (pin "B10") (pinfunction "SSRXn1_B10") (pintype "passive"))
    )
    (net (code "57") (name "unconnected-(J3-SSRXn2-PadA10)") (class "Default")
      (node (ref "J3") (pin "A10") (pinfunction "SSRXn2_A10") (pintype "passive"))
    )
    (net (code "58") (name "unconnected-(J3-SSRXp1-PadB11)") (class "Default")
      (node (ref "J3") (pin "B11") (pinfunction "SSRXp1_B11") (pintype "passive"))
    )
    (net (code "59") (name "unconnected-(J3-SSRXp2-PadA11)") (class "Default")
      (node (ref "J3") (pin "A11") (pinfunction "SSRXp2_A11") (pintype "passive"))
    )
    (net (code "60") (name "unconnected-(J3-SSTXn1-PadA3)") (class "Default")
      (node (ref "J3") (pin "A3") (pinfunction "SSTXn1_A3") (pintype "passive"))
    )
    (net (code "61") (name "unconnected-(J3-SSTXn2-PadB3)") (class "Default")
      (node (ref "J3") (pin "B3") (pinfunction "SSTXn2_B3") (pintype "passive"))
    )
    (net (code "62") (name "unconnected-(J3-SSTXp1-PadA2)") (class "Default")
      (node (ref "J3") (pin "A2") (pinfunction "SSTXp1_A2") (pintype "passive"))
    )
    (net (code "63") (name "unconnected-(J3-SSTXp2-PadB2)") (class "Default")
      (node (ref "J3") (pin "B2") (pinfunction "SSTXp2_B2") (pintype "passive"))
    )
    (net (code "64") (name "unconnected-(J4-SHIELD1-Pad5)") (class "Default")
      (node (ref "J4") (pin "5") (pinfunction "SHIELD1_5") (pintype "passive"))
    )
    (net (code "65") (name "unconnected-(J4-SHIELD2-Pad6)") (class "Default")
      (node (ref "J4") (pin "6") (pinfunction "SHIELD2_6") (pintype "passive"))
    )
    (net (code "66") (name "unconnected-(Q1-D2-Pad5)") (class "Default")
      (node (ref "Q1") (pin "5") (pinfunction "D2_5") (pintype "passive"))
    )
    (net (code "67") (name "unconnected-(Q4-D1-Pad2)") (class "Default")
      (node (ref "Q4") (pin "2") (pinfunction "D1_2") (pintype "passive"))
    )
    (net (code "68") (name "unconnected-(Q6-D1-Pad2)") (class "Default")
      (node (ref "Q6") (pin "2") (pinfunction "D1_2") (pintype "passive"))
    )
    (net (code "69") (name "unconnected-(Q7-D1-Pad2)") (class "Default")
      (node (ref "Q7") (pin "2") (pinfunction "D1_2") (pintype "passive"))
    )
    (net (code "70") (name "unconnected-(U1-TD-Pad4)") (class "Default")
      (node (ref "U1") (pin "4") (pinfunction "TD_4") (pintype "passive"))
    )
    (net (code "71") (name "unconnected-(U2-DMB-Pad40)") (class "Default")
      (node (ref "U2") (pin "40") (pinfunction "DMB_40") (pintype "passive"))
    )
    (net (code "72") (name "unconnected-(U2-DPB-Pad1)") (class "Default")
      (node (ref "U2") (pin "1") (pinfunction "DPB_1") (pintype "passive"))
    )
    (net (code "73") (name "unconnected-(U2-GATE_B-Pad31)") (class "Default")
      (node (ref "U2") (pin "31") (pinfunction "GATE_B_31") (pintype "passive"))
    )
    (net (code "74") (name "unconnected-(U2-VBUS_B-Pad30)") (class "Default")
      (node (ref "U2") (pin "30") (pinfunction "VBUS_B_30") (pintype "passive"))
    )
    (net (code "75") (name "unconnected-(U3-PA3-Pad4)") (class "Default")
      (node (ref "U3") (pin "4") (pinfunction "PA3_4") (pintype "passive"))
    )
    (net (code "76") (name "unconnected-(U3-PA7-Pad7)") (class "Default")
      (node (ref "U3") (pin "7") (pinfunction "PA7_7") (pintype "passive"))
    )
    (net (code "77") (name "unconnected-(U3-PB2-Pad6)") (class "Default")
      (node (ref "U3") (pin "6") (pinfunction "PB2_6") (pintype "passive"))
    )
  )
)
